# ColorBar.net
KiCad netlist of a schematic drawn in EAGLE
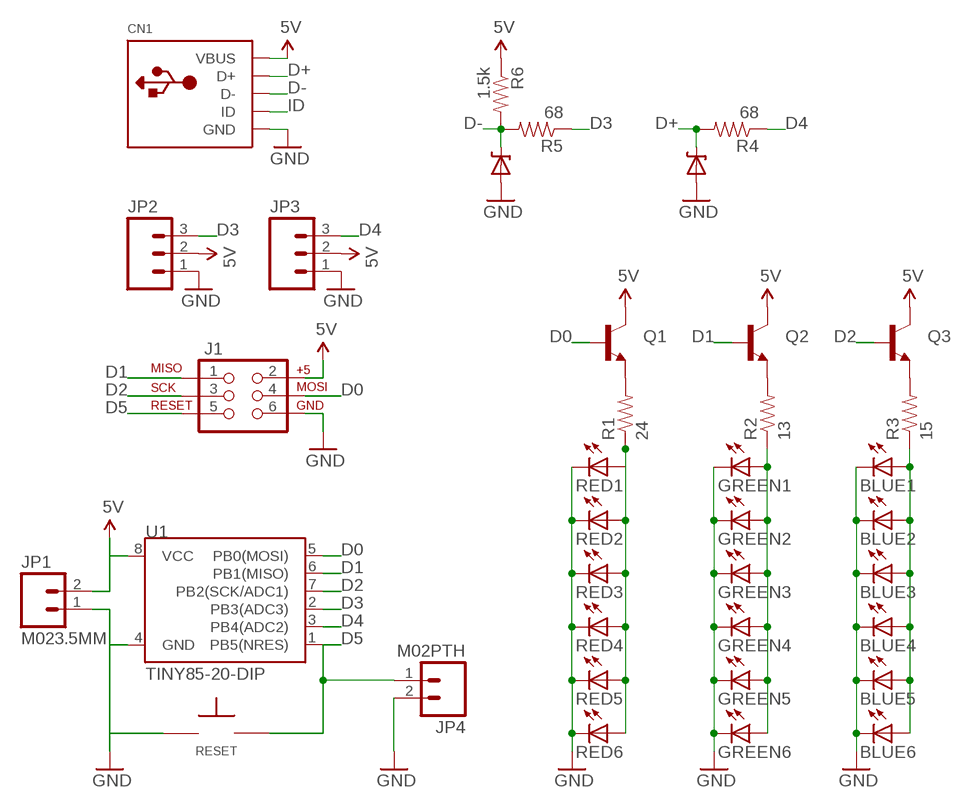
[diagram p0: schematic, sheet 1]

(export (version "E")
  (design (tool "Eeschema 10.0.6"))
  (components
    (comp (ref "BLUE1")
      (value "LEDOVAL")
      (footprint "eagle-import:LED-OVAL")
      (libsource (lib "eagle-import") (part "LEDOVAL"))
    )
    (comp (ref "BLUE2")
      (value "LEDOVAL")
      (footprint "eagle-import:LED-OVAL")
      (libsource (lib "eagle-import") (part "LEDOVAL"))
    )
    (comp (ref "BLUE3")
      (value "LEDOVAL")
      (footprint "eagle-import:LED-OVAL")
      (libsource (lib "eagle-import") (part "LEDOVAL"))
    )
    (comp (ref "BLUE4")
      (value "LEDOVAL")
      (footprint "eagle-import:LED-OVAL")
      (libsource (lib "eagle-import") (part "LEDOVAL"))
    )
    (comp (ref "BLUE5")
      (value "LEDOVAL")
      (footprint "eagle-import:LED-OVAL")
      (libsource (lib "eagle-import") (part "LEDOVAL"))
    )
    (comp (ref "BLUE6")
      (value "LEDOVAL")
      (footprint "eagle-import:LED-OVAL")
      (libsource (lib "eagle-import") (part "LEDOVAL"))
    )
    (comp (ref "CN1")
      (value "USBMOLEX")
      (footprint "eagle-import:USB-MINIB-THM-MOLEX")
      (libsource (lib "eagle-import") (part "USBMOLEX"))
    )
    (comp (ref "GREEN1")
      (value "LEDOVAL")
      (footprint "eagle-import:LED-OVAL")
      (libsource (lib "eagle-import") (part "LEDOVAL"))
    )
    (comp (ref "GREEN2")
      (value "LEDOVAL")
      (footprint "eagle-import:LED-OVAL")
      (libsource (lib "eagle-import") (part "LEDOVAL"))
    )
    (comp (ref "GREEN3")
      (value "LEDOVAL")
      (footprint "eagle-import:LED-OVAL")
      (libsource (lib "eagle-import") (part "LEDOVAL"))
    )
    (comp (ref "GREEN4")
      (value "LEDOVAL")
      (footprint "eagle-import:LED-OVAL")
      (libsource (lib "eagle-import") (part "LEDOVAL"))
    )
    (comp (ref "GREEN5")
      (value "LEDOVAL")
      (footprint "eagle-import:LED-OVAL")
      (libsource (lib "eagle-import") (part "LEDOVAL"))
    )
    (comp (ref "GREEN6")
      (value "LEDOVAL")
      (footprint "eagle-import:LED-OVAL")
      (libsource (lib "eagle-import") (part "LEDOVAL"))
    )
    (comp (ref "J1")
      (value "AVR_SPI_PRG_6LABELED")
      (footprint "eagle-import:2X3-NS")
      (libsource (lib "eagle-import") (part "AVR_SPI_PRG_6LABELED"))
    )
    (comp (ref "JP1")
      (value "M023.5MM")
      (footprint "eagle-import:SCREWTERMINAL-3.5MM-2")
      (libsource (lib "eagle-import") (part "M023.5MM"))
    )
    (comp (ref "JP2")
      (value "M03PTH")
      (footprint "eagle-import:1X03")
      (libsource (lib "eagle-import") (part "M03PTH"))
    )
    (comp (ref "JP3")
      (value "M03PTH")
      (footprint "eagle-import:1X03")
      (libsource (lib "eagle-import") (part "M03PTH"))
    )
    (comp (ref "JP4")
      (value "M02PTH")
      (footprint "eagle-import:1X02")
      (libsource (lib "eagle-import") (part "M02PTH"))
    )
    (comp (ref "Q1")
      (value "TRANSISTOR_NPNTO-92-AMMO")
      (footprint "eagle-import:TO-92-AMMO")
      (libsource (lib "eagle-import") (part "TRANSISTOR_NPNTO-92-AMMO"))
    )
    (comp (ref "Q2")
      (value "TRANSISTOR_NPNTO-92-AMMO")
      (footprint "eagle-import:TO-92-AMMO")
      (libsource (lib "eagle-import") (part "TRANSISTOR_NPNTO-92-AMMO"))
    )
    (comp (ref "Q3")
      (value "TRANSISTOR_NPNTO-92-AMMO")
      (footprint "eagle-import:TO-92-AMMO")
      (libsource (lib "eagle-import") (part "TRANSISTOR_NPNTO-92-AMMO"))
    )
    (comp (ref "R1")
      (value "24")
      (footprint "eagle-import:AXIAL-0.3")
      (libsource (lib "eagle-import") (part "RESISTORAXIAL-0.3"))
    )
    (comp (ref "R2")
      (value "13")
      (footprint "eagle-import:AXIAL-0.3")
      (libsource (lib "eagle-import") (part "RESISTORAXIAL-0.3"))
    )
    (comp (ref "R3")
      (value "15")
      (footprint "eagle-import:AXIAL-0.3")
      (libsource (lib "eagle-import") (part "RESISTORAXIAL-0.3"))
    )
    (comp (ref "R4")
      (value "68")
      (footprint "eagle-import:AXIAL-0.3")
      (libsource (lib "eagle-import") (part "RESISTORAXIAL-0.3"))
    )
    (comp (ref "R5")
      (value "68")
      (footprint "eagle-import:AXIAL-0.3")
      (libsource (lib "eagle-import") (part "RESISTORAXIAL-0.3"))
    )
    (comp (ref "R6")
      (value "1.5k")
      (footprint "eagle-import:AXIAL-0.3")
      (libsource (lib "eagle-import") (part "RESISTORAXIAL-0.3"))
    )
    (comp (ref "RED1")
      (value "LEDOVAL")
      (footprint "eagle-import:LED-OVAL")
      (libsource (lib "eagle-import") (part "LEDOVAL"))
    )
    (comp (ref "RED2")
      (value "LEDOVAL")
      (footprint "eagle-import:LED-OVAL")
      (libsource (lib "eagle-import") (part "LEDOVAL"))
    )
    (comp (ref "RED3")
      (value "LEDOVAL")
      (footprint "eagle-import:LED-OVAL")
      (libsource (lib "eagle-import") (part "LEDOVAL"))
    )
    (comp (ref "RED4")
      (value "LEDOVAL")
      (footprint "eagle-import:LED-OVAL")
      (libsource (lib "eagle-import") (part "LEDOVAL"))
    )
    (comp (ref "RED5")
      (value "LEDOVAL")
      (footprint "eagle-import:LED-OVAL")
      (libsource (lib "eagle-import") (part "LEDOVAL"))
    )
    (comp (ref "RED6")
      (value "LEDOVAL")
      (footprint "eagle-import:LED-OVAL")
      (libsource (lib "eagle-import") (part "LEDOVAL"))
    )
    (comp (ref "RESET")
      (value "TAC_SPST_NO")
      (footprint "eagle-import:TAC_SPST_NO")
      (libsource (lib "eagle-import") (part "TAC_SPST_NO"))
    )
    (comp (ref "U$1")
      (value "3.6")
      (footprint "eagle-import:DIODE-ZENER")
      (libsource (lib "eagle-import") (part "DIODE-ZENERPTH"))
    )
    (comp (ref "U$2")
      (value "3.6")
      (footprint "eagle-import:DIODE-ZENER")
      (libsource (lib "eagle-import") (part "DIODE-ZENERPTH"))
    )
    (comp (ref "U1")
      (value "TINY85-20-DIP")
      (footprint "eagle-import:DIP08")
      (libsource (lib "eagle-import") (part "ATTINY45TINY85-20-DIP"))
    )
  )
  (nets
    (net (code "1") (name "/D+") (class "Default")
      (node (ref "CN1") (pin "D+") (pinfunction "D+_D+") (pintype "bidirectional"))
      (node (ref "R4") (pin "P$2") (pinfunction "2_P$2") (pintype "passive"))
      (node (ref "U$2") (pin "P$1") (pinfunction "C_P$1") (pintype "passive"))
    )
    (net (code "2") (name "/D-") (class "Default")
      (node (ref "CN1") (pin "D-") (pinfunction "D-_D-") (pintype "bidirectional"))
      (node (ref "R5") (pin "P$2") (pinfunction "2_P$2") (pintype "passive"))
      (node (ref "R6") (pin "P$2") (pinfunction "2_P$2") (pintype "passive"))
      (node (ref "U$1") (pin "P$1") (pinfunction "C_P$1") (pintype "passive"))
    )
    (net (code "3") (name "/D0") (class "Default")
      (node (ref "J1") (pin "4") (pinfunction "MOSI_4") (pintype "passive"))
      (node (ref "Q1") (pin "2") (pinfunction "B_2") (pintype "passive"))
      (node (ref "U1") (pin "5") (pinfunction "PB0(MOSI)_5") (pintype "bidirectional"))
    )
    (net (code "4") (name "/D1") (class "Default")
      (node (ref "J1") (pin "1") (pinfunction "MISO_1") (pintype "passive"))
      (node (ref "Q2") (pin "2") (pinfunction "B_2") (pintype "passive"))
      (node (ref "U1") (pin "6") (pinfunction "PB1(MISO)_6") (pintype "bidirectional"))
    )
    (net (code "5") (name "/D2") (class "Default")
      (node (ref "J1") (pin "3") (pinfunction "SCK_3") (pintype "passive"))
      (node (ref "Q3") (pin "2") (pinfunction "B_2") (pintype "passive"))
      (node (ref "U1") (pin "7") (pinfunction "PB2(SCK/ADC1)_7") (pintype "bidirectional"))
    )
    (net (code "6") (name "/D3") (class "Default")
      (node (ref "JP2") (pin "3") (pinfunction "3_3") (pintype "passive"))
      (node (ref "R5") (pin "P$1") (pinfunction "1_P$1") (pintype "passive"))
      (node (ref "U1") (pin "2") (pinfunction "PB3(ADC3)_2") (pintype "bidirectional"))
    )
    (net (code "7") (name "/D4") (class "Default")
      (node (ref "JP3") (pin "3") (pinfunction "3_3") (pintype "passive"))
      (node (ref "R4") (pin "P$1") (pinfunction "1_P$1") (pintype "passive"))
      (node (ref "U1") (pin "3") (pinfunction "PB4(ADC2)_3") (pintype "bidirectional"))
    )
    (net (code "8") (name "/D5") (class "Default")
      (node (ref "J1") (pin "5") (pinfunction "RST_5") (pintype "passive"))
      (node (ref "JP4") (pin "1") (pinfunction "1_1") (pintype "passive"))
      (node (ref "RESET") (pin "P$2") (pinfunction "P$2_P$2") (pintype "bidirectional"))
      (node (ref "U1") (pin "1") (pinfunction "PB5(NRES)_1") (pintype "bidirectional"))
    )
    (net (code "9") (name "/ID") (class "Default")
      (node (ref "CN1") (pin "ID") (pinfunction "ID_ID") (pintype "bidirectional"))
    )
    (net (code "10") (name "5V") (class "Default")
      (node (ref "CN1") (pin "VBUS") (pinfunction "VBUS_VBUS") (pintype "power_in"))
      (node (ref "J1") (pin "2") (pinfunction "V+_2") (pintype "passive"))
      (node (ref "JP1") (pin "2") (pinfunction "2_2") (pintype "passive"))
      (node (ref "JP2") (pin "2") (pinfunction "2_2") (pintype "passive"))
      (node (ref "JP3") (pin "2") (pinfunction "2_2") (pintype "passive"))
      (node (ref "Q1") (pin "3") (pinfunction "C_3") (pintype "passive"))
      (node (ref "Q2") (pin "3") (pinfunction "C_3") (pintype "passive"))
      (node (ref "Q3") (pin "3") (pinfunction "C_3") (pintype "passive"))
      (node (ref "R6") (pin "P$1") (pinfunction "1_P$1") (pintype "passive"))
      (node (ref "U1") (pin "8") (pinfunction "VCC_8") (pintype "bidirectional"))
    )
    (net (code "11") (name "GND") (class "Default")
      (node (ref "BLUE1") (pin "CATHODE") (pinfunction "C_CATHODE") (pintype "passive"))
      (node (ref "BLUE2") (pin "CATHODE") (pinfunction "C_CATHODE") (pintype "passive"))
      (node (ref "BLUE3") (pin "CATHODE") (pinfunction "C_CATHODE") (pintype "passive"))
      (node (ref "BLUE4") (pin "CATHODE") (pinfunction "C_CATHODE") (pintype "passive"))
      (node (ref "BLUE5") (pin "CATHODE") (pinfunction "C_CATHODE") (pintype "passive"))
      (node (ref "BLUE6") (pin "CATHODE") (pinfunction "C_CATHODE") (pintype "passive"))
      (node (ref "CN1") (pin "GND") (pinfunction "GND_GND") (pintype "power_in"))
      (node (ref "GREEN1") (pin "CATHODE") (pinfunction "C_CATHODE") (pintype "passive"))
      (node (ref "GREEN2") (pin "CATHODE") (pinfunction "C_CATHODE") (pintype "passive"))
      (node (ref "GREEN3") (pin "CATHODE") (pinfunction "C_CATHODE") (pintype "passive"))
      (node (ref "GREEN4") (pin "CATHODE") (pinfunction "C_CATHODE") (pintype "passive"))
      (node (ref "GREEN5") (pin "CATHODE") (pinfunction "C_CATHODE") (pintype "passive"))
      (node (ref "GREEN6") (pin "CATHODE") (pinfunction "C_CATHODE") (pintype "passive"))
      (node (ref "J1") (pin "6") (pinfunction "GND_6") (pintype "passive"))
      (node (ref "JP1") (pin "1") (pinfunction "1_1") (pintype "passive"))
      (node (ref "JP2") (pin "1") (pinfunction "1_1") (pintype "passive"))
      (node (ref "JP3") (pin "1") (pinfunction "1_1") (pintype "passive"))
      (node (ref "JP4") (pin "2") (pinfunction "2_2") (pintype "passive"))
      (node (ref "RED1") (pin "CATHODE") (pinfunction "C_CATHODE") (pintype "passive"))
      (node (ref "RED2") (pin "CATHODE") (pinfunction "C_CATHODE") (pintype "passive"))
      (node (ref "RED3") (pin "CATHODE") (pinfunction "C_CATHODE") (pintype "passive"))
      (node (ref "RED4") (pin "CATHODE") (pinfunction "C_CATHODE") (pintype "passive"))
      (node (ref "RED5") (pin "CATHODE") (pinfunction "C_CATHODE") (pintype "passive"))
      (node (ref "RED6") (pin "CATHODE") (pinfunction "C_CATHODE") (pintype "passive"))
      (node (ref "RESET") (pin "P$1") (pinfunction "P$1_P$1") (pintype "bidirectional"))
      (node (ref "U$1") (pin "P$2") (pinfunction "A_P$2") (pintype "passive"))
      (node (ref "U$2") (pin "P$2") (pinfunction "A_P$2") (pintype "passive"))
      (node (ref "U1") (pin "4") (pinfunction "GND_4") (pintype "bidirectional"))
    )
    (net (code "12") (name "Net-(BLUE1-A)") (class "Default")
      (node (ref "BLUE1") (pin "ANODE") (pinfunction "A_ANODE") (pintype "passive"))
      (node (ref "BLUE2") (pin "ANODE") (pinfunction "A_ANODE") (pintype "passive"))
      (node (ref "BLUE3") (pin "ANODE") (pinfunction "A_ANODE") (pintype "passive"))
      (node (ref "BLUE4") (pin "ANODE") (pinfunction "A_ANODE") (pintype "passive"))
      (node (ref "BLUE5") (pin "ANODE") (pinfunction "A_ANODE") (pintype "passive"))
      (node (ref "BLUE6") (pin "ANODE") (pinfunction "A_ANODE") (pintype "passive"))
      (node (ref "R3") (pin "P$1") (pinfunction "1_P$1") (pintype "passive"))
    )
    (net (code "13") (name "Net-(GREEN1-A)") (class "Default")
      (node (ref "GREEN1") (pin "ANODE") (pinfunction "A_ANODE") (pintype "passive"))
      (node (ref "GREEN2") (pin "ANODE") (pinfunction "A_ANODE") (pintype "passive"))
      (node (ref "GREEN3") (pin "ANODE") (pinfunction "A_ANODE") (pintype "passive"))
      (node (ref "GREEN4") (pin "ANODE") (pinfunction "A_ANODE") (pintype "passive"))
      (node (ref "GREEN5") (pin "ANODE") (pinfunction "A_ANODE") (pintype "passive"))
      (node (ref "GREEN6") (pin "ANODE") (pinfunction "A_ANODE") (pintype "passive"))
      (node (ref "R2") (pin "P$1") (pinfunction "1_P$1") (pintype "passive"))
    )
    (net (code "14") (name "Net-(Q1-E)") (class "Default")
      (node (ref "Q1") (pin "1") (pinfunction "E_1") (pintype "passive"))
      (node (ref "R1") (pin "P$2") (pinfunction "2_P$2") (pintype "passive"))
    )
    (net (code "15") (name "Net-(Q2-E)") (class "Default")
      (node (ref "Q2") (pin "1") (pinfunction "E_1") (pintype "passive"))
      (node (ref "R2") (pin "P$2") (pinfunction "2_P$2") (pintype "passive"))
    )
    (net (code "16") (name "Net-(Q3-E)") (class "Default")
      (node (ref "Q3") (pin "1") (pinfunction "E_1") (pintype "passive"))
      (node (ref "R3") (pin "P$2") (pinfunction "2_P$2") (pintype "passive"))
    )
    (net (code "17") (name "Net-(R1-1)") (class "Default")
      (node (ref "R1") (pin "P$1") (pinfunction "1_P$1") (pintype "passive"))
      (node (ref "RED1") (pin "ANODE") (pinfunction "A_ANODE") (pintype "passive"))
      (node (ref "RED2") (pin "ANODE") (pinfunction "A_ANODE") (pintype "passive"))
      (node (ref "RED3") (pin "ANODE") (pinfunction "A_ANODE") (pintype "passive"))
      (node (ref "RED4") (pin "ANODE") (pinfunction "A_ANODE") (pintype "passive"))
      (node (ref "RED5") (pin "ANODE") (pinfunction "A_ANODE") (pintype "passive"))
      (node (ref "RED6") (pin "ANODE") (pinfunction "A_ANODE") (pintype "passive"))
    )
  )
)
